# ADS1298.net
KiCad netlist of a schematic drawn in Altium Designer
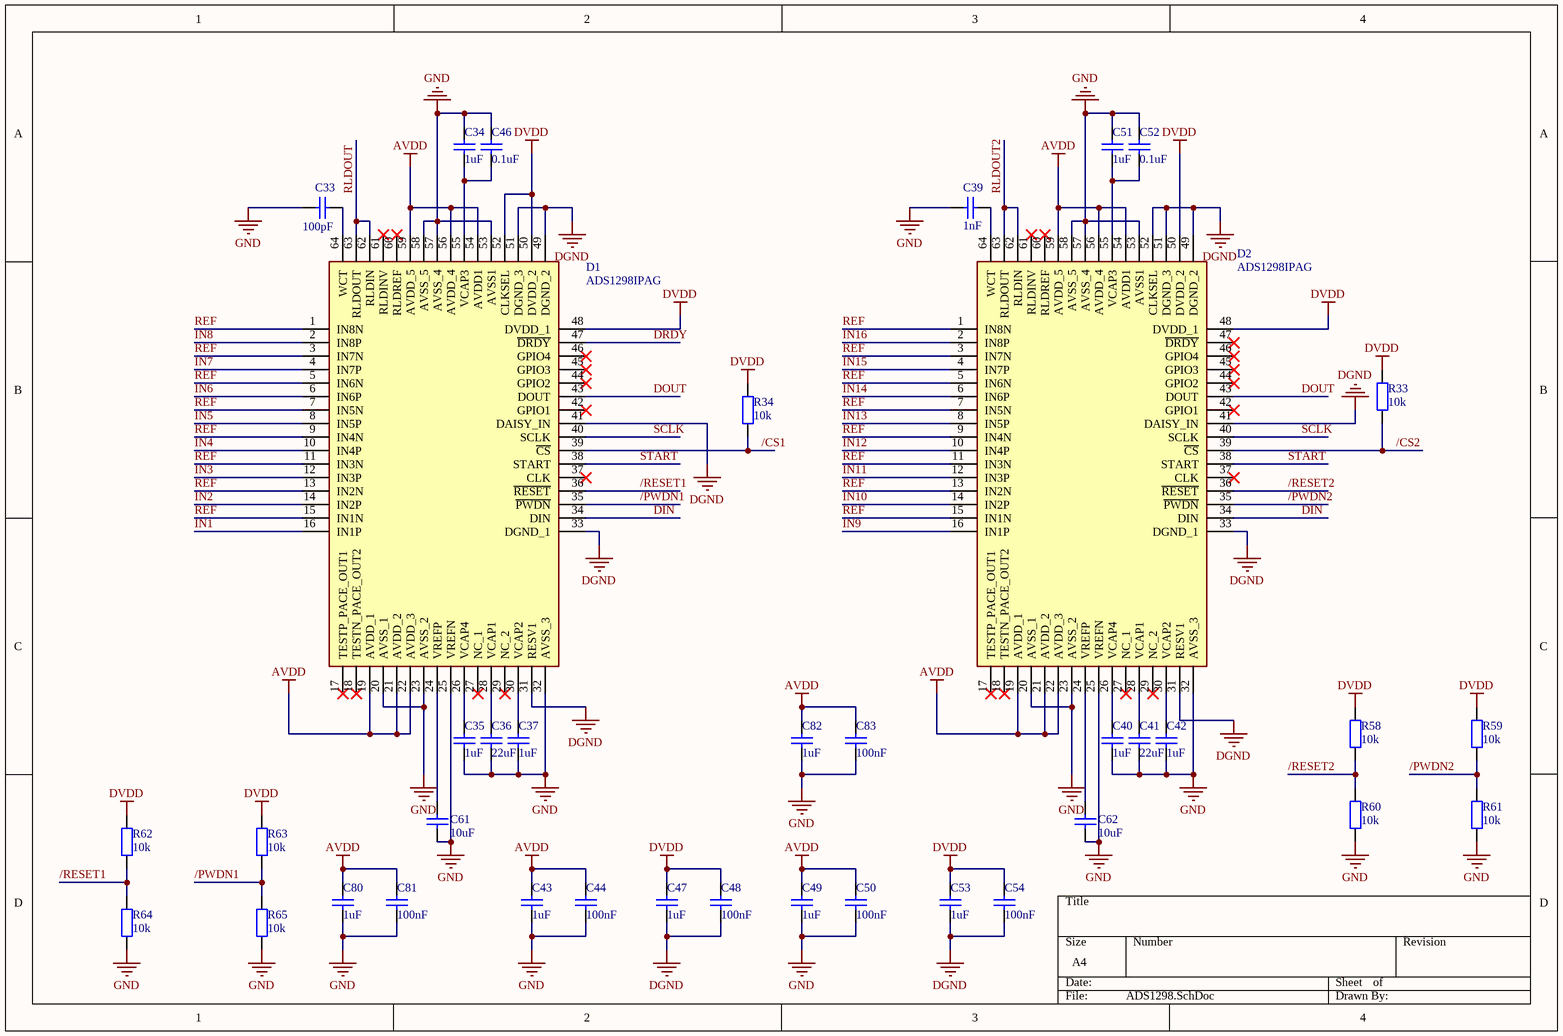
[diagram p0: ADS1298.SchDoc]

(export (version "E")
  (design (tool "Eeschema 10.0.6"))
  (components
    (comp (ref "C33")
      (value "100pF")
      (footprint "C0603")
      (description "Capacitor")
      (fields (field (name "PUBLISHER") "Altium Limited"))
      (libsource (lib "Miscellaneous Devices") (part "Cap"))
    )
    (comp (ref "C34")
      (value "1uF")
      (footprint "C0603")
      (description "Capacitor")
      (fields (field (name "PUBLISHER") "Altium Limited"))
      (libsource (lib "Miscellaneous Devices") (part "Cap"))
    )
    (comp (ref "C35")
      (value "1uF")
      (footprint "C0603")
      (description "Capacitor")
      (fields (field (name "PUBLISHER") "Altium Limited"))
      (libsource (lib "Miscellaneous Devices") (part "Cap"))
    )
    (comp (ref "C36")
      (value "22uF")
      (footprint "C0603")
      (description "Capacitor")
      (fields (field (name "PUBLISHER") "Altium Limited"))
      (libsource (lib "Miscellaneous Devices") (part "Cap"))
    )
    (comp (ref "C37")
      (value "1uF")
      (footprint "C0603")
      (description "Capacitor")
      (fields (field (name "PUBLISHER") "Altium Limited"))
      (libsource (lib "Miscellaneous Devices") (part "Cap"))
    )
    (comp (ref "C39")
      (value "1nF")
      (footprint "C0603")
      (description "Capacitor")
      (fields (field (name "PUBLISHER") "Altium Limited"))
      (libsource (lib "Miscellaneous Devices") (part "Cap"))
    )
    (comp (ref "C40")
      (value "1uF")
      (footprint "C0603")
      (description "Capacitor")
      (fields (field (name "PUBLISHER") "Altium Limited"))
      (libsource (lib "Miscellaneous Devices") (part "Cap"))
    )
    (comp (ref "C41")
      (value "22uF")
      (footprint "C0603")
      (description "Capacitor")
      (fields (field (name "PUBLISHER") "Altium Limited"))
      (libsource (lib "Miscellaneous Devices") (part "Cap"))
    )
    (comp (ref "C42")
      (value "1uF")
      (footprint "C0603")
      (description "Capacitor")
      (fields (field (name "PUBLISHER") "Altium Limited"))
      (libsource (lib "Miscellaneous Devices") (part "Cap"))
    )
    (comp (ref "C43")
      (value "1uF")
      (footprint "C0603")
      (description "Capacitor")
      (fields (field (name "PUBLISHER") "Altium Limited"))
      (libsource (lib "Miscellaneous Devices") (part "Cap"))
    )
    (comp (ref "C44")
      (value "100nF")
      (footprint "C0603")
      (description "Capacitor")
      (fields (field (name "PUBLISHER") "Altium Limited"))
      (libsource (lib "Miscellaneous Devices") (part "Cap"))
    )
    (comp (ref "C46")
      (value "0.1uF")
      (footprint "C0603")
      (description "Capacitor")
      (fields (field (name "PUBLISHER") "Altium Limited"))
      (libsource (lib "Miscellaneous Devices") (part "Cap"))
    )
    (comp (ref "C47")
      (value "1uF")
      (footprint "C0603")
      (description "Capacitor")
      (fields (field (name "PUBLISHER") "Altium Limited"))
      (libsource (lib "Miscellaneous Devices") (part "Cap"))
    )
    (comp (ref "C48")
      (value "100nF")
      (footprint "C0603")
      (description "Capacitor")
      (fields (field (name "PUBLISHER") "Altium Limited"))
      (libsource (lib "Miscellaneous Devices") (part "Cap"))
    )
    (comp (ref "C49")
      (value "1uF")
      (footprint "C0603")
      (description "Capacitor")
      (fields (field (name "PUBLISHER") "Altium Limited"))
      (libsource (lib "Miscellaneous Devices") (part "Cap"))
    )
    (comp (ref "C50")
      (value "100nF")
      (footprint "C0603")
      (description "Capacitor")
      (fields (field (name "PUBLISHER") "Altium Limited"))
      (libsource (lib "Miscellaneous Devices") (part "Cap"))
    )
    (comp (ref "C51")
      (value "1uF")
      (footprint "C0603")
      (description "Capacitor")
      (fields (field (name "PUBLISHER") "Altium Limited"))
      (libsource (lib "Miscellaneous Devices") (part "Cap"))
    )
    (comp (ref "C52")
      (value "0.1uF")
      (footprint "C0603")
      (description "Capacitor")
      (fields (field (name "PUBLISHER") "Altium Limited"))
      (libsource (lib "Miscellaneous Devices") (part "Cap"))
    )
    (comp (ref "C53")
      (value "1uF")
      (footprint "C0603")
      (description "Capacitor")
      (fields (field (name "PUBLISHER") "Altium Limited"))
      (libsource (lib "Miscellaneous Devices") (part "Cap"))
    )
    (comp (ref "C54")
      (value "100nF")
      (footprint "C0603")
      (description "Capacitor")
      (fields (field (name "PUBLISHER") "Altium Limited"))
      (libsource (lib "Miscellaneous Devices") (part "Cap"))
    )
    (comp (ref "C61")
      (value "10uF")
      (footprint "C0603")
      (description "Capacitor")
      (fields (field (name "PUBLISHER") "Altium Limited"))
      (libsource (lib "Miscellaneous Devices") (part "Cap"))
    )
    (comp (ref "C62")
      (value "10uF")
      (footprint "C0603")
      (description "Capacitor")
      (fields (field (name "PUBLISHER") "Altium Limited"))
      (libsource (lib "Miscellaneous Devices") (part "Cap"))
    )
    (comp (ref "C80")
      (value "1uF")
      (footprint "C0603")
      (description "Capacitor")
      (fields (field (name "PUBLISHER") "Altium Limited"))
      (libsource (lib "Miscellaneous Devices") (part "Cap"))
    )
    (comp (ref "C81")
      (value "100nF")
      (footprint "C0603")
      (description "Capacitor")
      (fields (field (name "PUBLISHER") "Altium Limited"))
      (libsource (lib "Miscellaneous Devices") (part "Cap"))
    )
    (comp (ref "C82")
      (value "1uF")
      (footprint "C0603")
      (description "Capacitor")
      (fields (field (name "PUBLISHER") "Altium Limited"))
      (libsource (lib "Miscellaneous Devices") (part "Cap"))
    )
    (comp (ref "C83")
      (value "100nF")
      (footprint "C0603")
      (description "Capacitor")
      (fields (field (name "PUBLISHER") "Altium Limited"))
      (libsource (lib "Miscellaneous Devices") (part "Cap"))
    )
    (comp (ref "D1")
      (value "ADS1298IPAG")
      (footprint "ADS1298")
      (description "Integrated Circuit")
      (fields (field (name "MOUSER PART NUMBER") "595-ADS1298IPAG"))
      (libsource (lib "*") (part "ADS1298IPAG"))
    )
    (comp (ref "D2")
      (value "ADS1298IPAG")
      (footprint "ADS1298")
      (description "Integrated Circuit")
      (fields (field (name "MOUSER PART NUMBER") "595-ADS1298IPAG"))
      (libsource (lib "*") (part "ADS1298IPAG"))
    )
    (comp (ref "R33")
      (value "10k")
      (footprint "RES0603")
      (description "Resistor")
      (fields (field (name "PUBLISHER") "Altium Limited"))
      (libsource (lib "Miscellaneous Devices") (part "Res2"))
    )
    (comp (ref "R34")
      (value "10k")
      (footprint "RES0603")
      (description "Resistor")
      (fields (field (name "PUBLISHER") "Altium Limited"))
      (libsource (lib "Miscellaneous Devices") (part "Res2"))
    )
    (comp (ref "R58")
      (value "10k")
      (footprint "RES0603")
      (description "Resistor")
      (fields (field (name "PUBLISHER") "Altium Limited"))
      (libsource (lib "Miscellaneous Devices") (part "Res2"))
    )
    (comp (ref "R59")
      (value "10k")
      (footprint "RES0603")
      (description "Resistor")
      (fields (field (name "PUBLISHER") "Altium Limited"))
      (libsource (lib "Miscellaneous Devices") (part "Res2"))
    )
    (comp (ref "R60")
      (value "10k")
      (footprint "RES0603")
      (description "Resistor")
      (fields (field (name "PUBLISHER") "Altium Limited"))
      (libsource (lib "Miscellaneous Devices") (part "Res2"))
    )
    (comp (ref "R61")
      (value "10k")
      (footprint "RES0603")
      (description "Resistor")
      (fields (field (name "PUBLISHER") "Altium Limited"))
      (libsource (lib "Miscellaneous Devices") (part "Res2"))
    )
    (comp (ref "R62")
      (value "10k")
      (footprint "RES0603")
      (description "Resistor")
      (fields (field (name "PUBLISHER") "Altium Limited"))
      (libsource (lib "Miscellaneous Devices") (part "Res2"))
    )
    (comp (ref "R63")
      (value "10k")
      (footprint "RES0603")
      (description "Resistor")
      (fields (field (name "PUBLISHER") "Altium Limited"))
      (libsource (lib "Miscellaneous Devices") (part "Res2"))
    )
    (comp (ref "R64")
      (value "10k")
      (footprint "RES0603")
      (description "Resistor")
      (fields (field (name "PUBLISHER") "Altium Limited"))
      (libsource (lib "Miscellaneous Devices") (part "Res2"))
    )
    (comp (ref "R65")
      (value "10k")
      (footprint "RES0603")
      (description "Resistor")
      (fields (field (name "PUBLISHER") "Altium Limited"))
      (libsource (lib "Miscellaneous Devices") (part "Res2"))
    )
  )
  (nets
    (net (code "1") (name "/DIN") (class "Default")
      (node (ref "D1") (pin "34") (pinfunction "DIN_34") (pintype "passive"))
      (node (ref "D2") (pin "34") (pinfunction "DIN_34") (pintype "passive"))
    )
    (net (code "2") (name "/DOUT") (class "Default")
      (node (ref "D1") (pin "43") (pinfunction "DOUT_43") (pintype "passive"))
      (node (ref "D2") (pin "43") (pinfunction "DOUT_43") (pintype "passive"))
    )
    (net (code "3") (name "/DRDY") (class "Default")
      (node (ref "D1") (pin "47") (pinfunction "~{DRDY}_47") (pintype "passive"))
    )
    (net (code "4") (name "/IN1") (class "Default")
      (node (ref "D1") (pin "16") (pinfunction "IN1P_16") (pintype "passive"))
    )
    (net (code "5") (name "/IN2") (class "Default")
      (node (ref "D1") (pin "14") (pinfunction "IN2P_14") (pintype "passive"))
    )
    (net (code "6") (name "/IN3") (class "Default")
      (node (ref "D1") (pin "12") (pinfunction "IN3P_12") (pintype "passive"))
    )
    (net (code "7") (name "/IN4") (class "Default")
      (node (ref "D1") (pin "10") (pinfunction "IN4P_10") (pintype "passive"))
    )
    (net (code "8") (name "/IN5") (class "Default")
      (node (ref "D1") (pin "8") (pinfunction "IN5P_8") (pintype "passive"))
    )
    (net (code "9") (name "/IN6") (class "Default")
      (node (ref "D1") (pin "6") (pinfunction "IN6P_6") (pintype "passive"))
    )
    (net (code "10") (name "/IN7") (class "Default")
      (node (ref "D1") (pin "4") (pinfunction "IN7P_4") (pintype "passive"))
    )
    (net (code "11") (name "/IN8") (class "Default")
      (node (ref "D1") (pin "2") (pinfunction "IN8P_2") (pintype "passive"))
    )
    (net (code "12") (name "/IN9") (class "Default")
      (node (ref "D2") (pin "16") (pinfunction "IN1P_16") (pintype "passive"))
    )
    (net (code "13") (name "/IN10") (class "Default")
      (node (ref "D2") (pin "14") (pinfunction "IN2P_14") (pintype "passive"))
    )
    (net (code "14") (name "/IN11") (class "Default")
      (node (ref "D2") (pin "12") (pinfunction "IN3P_12") (pintype "passive"))
    )
    (net (code "15") (name "/IN12") (class "Default")
      (node (ref "D2") (pin "10") (pinfunction "IN4P_10") (pintype "passive"))
    )
    (net (code "16") (name "/IN13") (class "Default")
      (node (ref "D2") (pin "8") (pinfunction "IN5P_8") (pintype "passive"))
    )
    (net (code "17") (name "/IN14") (class "Default")
      (node (ref "D2") (pin "6") (pinfunction "IN6P_6") (pintype "passive"))
    )
    (net (code "18") (name "/IN15") (class "Default")
      (node (ref "D2") (pin "4") (pinfunction "IN7P_4") (pintype "passive"))
    )
    (net (code "19") (name "/IN16") (class "Default")
      (node (ref "D2") (pin "2") (pinfunction "IN8P_2") (pintype "passive"))
    )
    (net (code "20") (name "/REF") (class "Default")
      (node (ref "D1") (pin "1") (pinfunction "IN8N_1") (pintype "passive"))
      (node (ref "D1") (pin "11") (pinfunction "IN3N_11") (pintype "passive"))
      (node (ref "D1") (pin "13") (pinfunction "IN2N_13") (pintype "passive"))
      (node (ref "D1") (pin "15") (pinfunction "IN1N_15") (pintype "passive"))
      (node (ref "D1") (pin "3") (pinfunction "IN7N_3") (pintype "passive"))
      (node (ref "D1") (pin "5") (pinfunction "IN6N_5") (pintype "passive"))
      (node (ref "D1") (pin "7") (pinfunction "IN5N_7") (pintype "passive"))
      (node (ref "D1") (pin "9") (pinfunction "IN4N_9") (pintype "passive"))
      (node (ref "D2") (pin "1") (pinfunction "IN8N_1") (pintype "passive"))
      (node (ref "D2") (pin "11") (pinfunction "IN3N_11") (pintype "passive"))
      (node (ref "D2") (pin "13") (pinfunction "IN2N_13") (pintype "passive"))
      (node (ref "D2") (pin "15") (pinfunction "IN1N_15") (pintype "passive"))
      (node (ref "D2") (pin "3") (pinfunction "IN7N_3") (pintype "passive"))
      (node (ref "D2") (pin "5") (pinfunction "IN6N_5") (pintype "passive"))
      (node (ref "D2") (pin "7") (pinfunction "IN5N_7") (pintype "passive"))
      (node (ref "D2") (pin "9") (pinfunction "IN4N_9") (pintype "passive"))
    )
    (net (code "21") (name "/RLDOUT") (class "Default")
      (node (ref "D1") (pin "62") (pinfunction "RLDIN_62") (pintype "passive"))
      (node (ref "D1") (pin "63") (pinfunction "RLDOUT_63") (pintype "passive"))
    )
    (net (code "22") (name "/RLDOUT2") (class "Default")
      (node (ref "D2") (pin "62") (pinfunction "RLDIN_62") (pintype "passive"))
      (node (ref "D2") (pin "63") (pinfunction "RLDOUT_63") (pintype "passive"))
    )
    (net (code "23") (name "/SCLK") (class "Default")
      (node (ref "D1") (pin "40") (pinfunction "SCLK_40") (pintype "passive"))
      (node (ref "D2") (pin "40") (pinfunction "SCLK_40") (pintype "passive"))
    )
    (net (code "24") (name "/START") (class "Default")
      (node (ref "D1") (pin "38") (pinfunction "START_38") (pintype "passive"))
      (node (ref "D2") (pin "38") (pinfunction "START_38") (pintype "passive"))
    )
    (net (code "25") (name "/{slash}CS1") (class "Default")
      (node (ref "D1") (pin "39") (pinfunction "~{CS}_39") (pintype "passive"))
      (node (ref "R34") (pin "1") (pinfunction "1_1") (pintype "passive"))
    )
    (net (code "26") (name "/{slash}CS2") (class "Default")
      (node (ref "D2") (pin "39") (pinfunction "~{CS}_39") (pintype "passive"))
      (node (ref "R33") (pin "1") (pinfunction "1_1") (pintype "passive"))
    )
    (net (code "27") (name "/{slash}PWDN1") (class "Default")
      (node (ref "D1") (pin "35") (pinfunction "~{PWDN}_35") (pintype "passive"))
      (node (ref "R63") (pin "1") (pinfunction "1_1") (pintype "passive"))
      (node (ref "R65") (pin "2") (pinfunction "2_2") (pintype "passive"))
    )
    (net (code "28") (name "/{slash}PWDN2") (class "Default")
      (node (ref "D2") (pin "35") (pinfunction "~{PWDN}_35") (pintype "passive"))
      (node (ref "R59") (pin "1") (pinfunction "1_1") (pintype "passive"))
      (node (ref "R61") (pin "2") (pinfunction "2_2") (pintype "passive"))
    )
    (net (code "29") (name "/{slash}RESET1") (class "Default")
      (node (ref "D1") (pin "36") (pinfunction "~{RESET}_36") (pintype "passive"))
      (node (ref "R62") (pin "1") (pinfunction "1_1") (pintype "passive"))
      (node (ref "R64") (pin "2") (pinfunction "2_2") (pintype "passive"))
    )
    (net (code "30") (name "/{slash}RESET2") (class "Default")
      (node (ref "D2") (pin "36") (pinfunction "~{RESET}_36") (pintype "passive"))
      (node (ref "R58") (pin "1") (pinfunction "1_1") (pintype "passive"))
      (node (ref "R60") (pin "2") (pinfunction "2_2") (pintype "passive"))
    )
    (net (code "31") (name "AVDD") (class "Default")
      (node (ref "C43") (pin "1") (pinfunction "1_1") (pintype "passive"))
      (node (ref "C44") (pin "1") (pinfunction "1_1") (pintype "passive"))
      (node (ref "C49") (pin "1") (pinfunction "1_1") (pintype "passive"))
      (node (ref "C50") (pin "1") (pinfunction "1_1") (pintype "passive"))
      (node (ref "C80") (pin "1") (pinfunction "1_1") (pintype "passive"))
      (node (ref "C81") (pin "1") (pinfunction "1_1") (pintype "passive"))
      (node (ref "C82") (pin "1") (pinfunction "1_1") (pintype "passive"))
      (node (ref "C83") (pin "1") (pinfunction "1_1") (pintype "passive"))
      (node (ref "D1") (pin "19") (pinfunction "AVDD_1_19") (pintype "passive"))
      (node (ref "D1") (pin "21") (pinfunction "AVDD_2_21") (pintype "passive"))
      (node (ref "D1") (pin "22") (pinfunction "AVDD_3_22") (pintype "passive"))
      (node (ref "D1") (pin "54") (pinfunction "AVDD1_54") (pintype "passive"))
      (node (ref "D1") (pin "56") (pinfunction "AVDD_4_56") (pintype "passive"))
      (node (ref "D1") (pin "59") (pinfunction "AVDD_5_59") (pintype "passive"))
      (node (ref "D2") (pin "19") (pinfunction "AVDD_1_19") (pintype "passive"))
      (node (ref "D2") (pin "21") (pinfunction "AVDD_2_21") (pintype "passive"))
      (node (ref "D2") (pin "22") (pinfunction "AVDD_3_22") (pintype "passive"))
      (node (ref "D2") (pin "54") (pinfunction "AVDD1_54") (pintype "passive"))
      (node (ref "D2") (pin "56") (pinfunction "AVDD_4_56") (pintype "passive"))
      (node (ref "D2") (pin "59") (pinfunction "AVDD_5_59") (pintype "passive"))
    )
    (net (code "32") (name "DGND") (class "Default")
      (node (ref "C47") (pin "2") (pinfunction "2_2") (pintype "passive"))
      (node (ref "C48") (pin "2") (pinfunction "2_2") (pintype "passive"))
      (node (ref "C53") (pin "2") (pinfunction "2_2") (pintype "passive"))
      (node (ref "C54") (pin "2") (pinfunction "2_2") (pintype "passive"))
      (node (ref "D1") (pin "31") (pinfunction "RESV1_31") (pintype "passive"))
      (node (ref "D1") (pin "33") (pinfunction "DGND_1_33") (pintype "passive"))
      (node (ref "D1") (pin "41") (pinfunction "DAISY_IN_41") (pintype "passive"))
      (node (ref "D1") (pin "49") (pinfunction "DGND_2_49") (pintype "passive"))
      (node (ref "D1") (pin "51") (pinfunction "DGND_3_51") (pintype "passive"))
      (node (ref "D2") (pin "31") (pinfunction "RESV1_31") (pintype "passive"))
      (node (ref "D2") (pin "33") (pinfunction "DGND_1_33") (pintype "passive"))
      (node (ref "D2") (pin "41") (pinfunction "DAISY_IN_41") (pintype "passive"))
      (node (ref "D2") (pin "49") (pinfunction "DGND_2_49") (pintype "passive"))
      (node (ref "D2") (pin "51") (pinfunction "DGND_3_51") (pintype "passive"))
      (node (ref "D2") (pin "52") (pinfunction "CLKSEL_52") (pintype "passive"))
    )
    (net (code "33") (name "DVDD") (class "Default")
      (node (ref "C47") (pin "1") (pinfunction "1_1") (pintype "passive"))
      (node (ref "C48") (pin "1") (pinfunction "1_1") (pintype "passive"))
      (node (ref "C53") (pin "1") (pinfunction "1_1") (pintype "passive"))
      (node (ref "C54") (pin "1") (pinfunction "1_1") (pintype "passive"))
      (node (ref "D1") (pin "48") (pinfunction "DVDD_1_48") (pintype "passive"))
      (node (ref "D1") (pin "50") (pinfunction "DVDD_2_50") (pintype "passive"))
      (node (ref "D1") (pin "52") (pinfunction "CLKSEL_52") (pintype "passive"))
      (node (ref "D2") (pin "48") (pinfunction "DVDD_1_48") (pintype "passive"))
      (node (ref "D2") (pin "50") (pinfunction "DVDD_2_50") (pintype "passive"))
      (node (ref "R33") (pin "2") (pinfunction "2_2") (pintype "passive"))
      (node (ref "R34") (pin "2") (pinfunction "2_2") (pintype "passive"))
      (node (ref "R58") (pin "2") (pinfunction "2_2") (pintype "passive"))
      (node (ref "R59") (pin "2") (pinfunction "2_2") (pintype "passive"))
      (node (ref "R62") (pin "2") (pinfunction "2_2") (pintype "passive"))
      (node (ref "R63") (pin "2") (pinfunction "2_2") (pintype "passive"))
    )
    (net (code "34") (name "GND") (class "Default")
      (node (ref "C33") (pin "2") (pinfunction "2_2") (pintype "passive"))
      (node (ref "C34") (pin "2") (pinfunction "2_2") (pintype "passive"))
      (node (ref "C35") (pin "2") (pinfunction "2_2") (pintype "passive"))
      (node (ref "C36") (pin "2") (pinfunction "2_2") (pintype "passive"))
      (node (ref "C37") (pin "2") (pinfunction "2_2") (pintype "passive"))
      (node (ref "C39") (pin "2") (pinfunction "2_2") (pintype "passive"))
      (node (ref "C40") (pin "2") (pinfunction "2_2") (pintype "passive"))
      (node (ref "C41") (pin "2") (pinfunction "2_2") (pintype "passive"))
      (node (ref "C42") (pin "2") (pinfunction "2_2") (pintype "passive"))
      (node (ref "C43") (pin "2") (pinfunction "2_2") (pintype "passive"))
      (node (ref "C44") (pin "2") (pinfunction "2_2") (pintype "passive"))
      (node (ref "C46") (pin "2") (pinfunction "2_2") (pintype "passive"))
      (node (ref "C49") (pin "2") (pinfunction "2_2") (pintype "passive"))
      (node (ref "C50") (pin "2") (pinfunction "2_2") (pintype "passive"))
      (node (ref "C51") (pin "2") (pinfunction "2_2") (pintype "passive"))
      (node (ref "C52") (pin "2") (pinfunction "2_2") (pintype "passive"))
      (node (ref "C61") (pin "1") (pinfunction "1_1") (pintype "passive"))
      (node (ref "C62") (pin "1") (pinfunction "1_1") (pintype "passive"))
      (node (ref "C80") (pin "2") (pinfunction "2_2") (pintype "passive"))
      (node (ref "C81") (pin "2") (pinfunction "2_2") (pintype "passive"))
      (node (ref "C82") (pin "2") (pinfunction "2_2") (pintype "passive"))
      (node (ref "C83") (pin "2") (pinfunction "2_2") (pintype "passive"))
      (node (ref "D1") (pin "20") (pinfunction "AVSS_1_20") (pintype "passive"))
      (node (ref "D1") (pin "23") (pinfunction "AVSS_2_23") (pintype "passive"))
      (node (ref "D1") (pin "25") (pinfunction "VREFN_25") (pintype "passive"))
      (node (ref "D1") (pin "32") (pinfunction "AVSS_3_32") (pintype "passive"))
      (node (ref "D1") (pin "53") (pinfunction "AVSS1_53") (pintype "passive"))
      (node (ref "D1") (pin "57") (pinfunction "AVSS_4_57") (pintype "passive"))
      (node (ref "D1") (pin "58") (pinfunction "AVSS_5_58") (pintype "passive"))
      (node (ref "D2") (pin "20") (pinfunction "AVSS_1_20") (pintype "passive"))
      (node (ref "D2") (pin "23") (pinfunction "AVSS_2_23") (pintype "passive"))
      (node (ref "D2") (pin "25") (pinfunction "VREFN_25") (pintype "passive"))
      (node (ref "D2") (pin "32") (pinfunction "AVSS_3_32") (pintype "passive"))
      (node (ref "D2") (pin "53") (pinfunction "AVSS1_53") (pintype "passive"))
      (node (ref "D2") (pin "57") (pinfunction "AVSS_4_57") (pintype "passive"))
      (node (ref "D2") (pin "58") (pinfunction "AVSS_5_58") (pintype "passive"))
      (node (ref "R60") (pin "1") (pinfunction "1_1") (pintype "passive"))
      (node (ref "R61") (pin "1") (pinfunction "1_1") (pintype "passive"))
      (node (ref "R64") (pin "1") (pinfunction "1_1") (pintype "passive"))
      (node (ref "R65") (pin "1") (pinfunction "1_1") (pintype "passive"))
    )
    (net (code "35") (name "Net-(D1-VCAP1)") (class "Default")
      (node (ref "C36") (pin "1") (pinfunction "1_1") (pintype "passive"))
      (node (ref "D1") (pin "28") (pinfunction "VCAP1_28") (pintype "passive"))
    )
    (net (code "36") (name "Net-(D1-VCAP2)") (class "Default")
      (node (ref "C37") (pin "1") (pinfunction "1_1") (pintype "passive"))
      (node (ref "D1") (pin "30") (pinfunction "VCAP2_30") (pintype "passive"))
    )
    (net (code "37") (name "Net-(D1-VCAP3)") (class "Default")
      (node (ref "C34") (pin "1") (pinfunction "1_1") (pintype "passive"))
      (node (ref "C46") (pin "1") (pinfunction "1_1") (pintype "passive"))
      (node (ref "D1") (pin "55") (pinfunction "VCAP3_55") (pintype "passive"))
    )
    (net (code "38") (name "Net-(D1-VCAP4)") (class "Default")
      (node (ref "C35") (pin "1") (pinfunction "1_1") (pintype "passive"))
      (node (ref "D1") (pin "26") (pinfunction "VCAP4_26") (pintype "passive"))
    )
    (net (code "39") (name "Net-(D1-VREFP)") (class "Default")
      (node (ref "C61") (pin "2") (pinfunction "2_2") (pintype "passive"))
      (node (ref "D1") (pin "24") (pinfunction "VREFP_24") (pintype "passive"))
    )
    (net (code "40") (name "Net-(D1-WCT)") (class "Default")
      (node (ref "C33") (pin "1") (pinfunction "1_1") (pintype "passive"))
      (node (ref "D1") (pin "64") (pinfunction "WCT_64") (pintype "passive"))
    )
    (net (code "41") (name "Net-(D2-VCAP1)") (class "Default")
      (node (ref "C41") (pin "1") (pinfunction "1_1") (pintype "passive"))
      (node (ref "D2") (pin "28") (pinfunction "VCAP1_28") (pintype "passive"))
    )
    (net (code "42") (name "Net-(D2-VCAP2)") (class "Default")
      (node (ref "C42") (pin "1") (pinfunction "1_1") (pintype "passive"))
      (node (ref "D2") (pin "30") (pinfunction "VCAP2_30") (pintype "passive"))
    )
    (net (code "43") (name "Net-(D2-VCAP3)") (class "Default")
      (node (ref "C51") (pin "1") (pinfunction "1_1") (pintype "passive"))
      (node (ref "C52") (pin "1") (pinfunction "1_1") (pintype "passive"))
      (node (ref "D2") (pin "55") (pinfunction "VCAP3_55") (pintype "passive"))
    )
    (net (code "44") (name "Net-(D2-VCAP4)") (class "Default")
      (node (ref "C40") (pin "1") (pinfunction "1_1") (pintype "passive"))
      (node (ref "D2") (pin "26") (pinfunction "VCAP4_26") (pintype "passive"))
    )
    (net (code "45") (name "Net-(D2-VREFP)") (class "Default")
      (node (ref "C62") (pin "2") (pinfunction "2_2") (pintype "passive"))
      (node (ref "D2") (pin "24") (pinfunction "VREFP_24") (pintype "passive"))
    )
    (net (code "46") (name "Net-(D2-WCT)") (class "Default")
      (node (ref "C39") (pin "1") (pinfunction "1_1") (pintype "passive"))
      (node (ref "D2") (pin "64") (pinfunction "WCT_64") (pintype "passive"))
    )
    (net (code "47") (name "unconnected-(D1-CLK-Pad37)") (class "Default")
      (node (ref "D1") (pin "37") (pinfunction "CLK_37") (pintype "passive+no_connect"))
    )
    (net (code "48") (name "unconnected-(D1-GPIO1-Pad42)") (class "Default")
      (node (ref "D1") (pin "42") (pinfunction "GPIO1_42") (pintype "passive+no_connect"))
    )
    (net (code "49") (name "unconnected-(D1-GPIO2-Pad44)") (class "Default")
      (node (ref "D1") (pin "44") (pinfunction "GPIO2_44") (pintype "passive+no_connect"))
    )
    (net (code "50") (name "unconnected-(D1-GPIO3-Pad45)") (class "Default")
      (node (ref "D1") (pin "45") (pinfunction "GPIO3_45") (pintype "passive+no_connect"))
    )
    (net (code "51") (name "unconnected-(D1-GPIO4-Pad46)") (class "Default")
      (node (ref "D1") (pin "46") (pinfunction "GPIO4_46") (pintype "passive+no_connect"))
    )
    (net (code "52") (name "unconnected-(D1-NC_1-Pad27)") (class "Default")
      (node (ref "D1") (pin "27") (pinfunction "NC_1_27") (pintype "passive+no_connect"))
    )
    (net (code "53") (name "unconnected-(D1-NC_2-Pad29)") (class "Default")
      (node (ref "D1") (pin "29") (pinfunction "NC_2_29") (pintype "passive+no_connect"))
    )
    (net (code "54") (name "unconnected-(D1-RLDINV-Pad61)") (class "Default")
      (node (ref "D1") (pin "61") (pinfunction "RLDINV_61") (pintype "passive+no_connect"))
    )
    (net (code "55") (name "unconnected-(D1-RLDREF-Pad60)") (class "Default")
      (node (ref "D1") (pin "60") (pinfunction "RLDREF_60") (pintype "passive+no_connect"))
    )
    (net (code "56") (name "unconnected-(D1-TESTN_PACE_OUT2-Pad18)") (class "Default")
      (node (ref "D1") (pin "18") (pinfunction "TESTN_PACE_OUT2_18") (pintype "passive+no_connect"))
    )
    (net (code "57") (name "unconnected-(D1-TESTP_PACE_OUT1-Pad17)") (class "Default")
      (node (ref "D1") (pin "17") (pinfunction "TESTP_PACE_OUT1_17") (pintype "passive+no_connect"))
    )
    (net (code "58") (name "unconnected-(D2-CLK-Pad37)") (class "Default")
      (node (ref "D2") (pin "37") (pinfunction "CLK_37") (pintype "passive+no_connect"))
    )
    (net (code "59") (name "unconnected-(D2-GPIO1-Pad42)") (class "Default")
      (node (ref "D2") (pin "42") (pinfunction "GPIO1_42") (pintype "passive+no_connect"))
    )
    (net (code "60") (name "unconnected-(D2-GPIO2-Pad44)") (class "Default")
      (node (ref "D2") (pin "44") (pinfunction "GPIO2_44") (pintype "passive+no_connect"))
    )
    (net (code "61") (name "unconnected-(D2-GPIO3-Pad45)") (class "Default")
      (node (ref "D2") (pin "45") (pinfunction "GPIO3_45") (pintype "passive+no_connect"))
    )
    (net (code "62") (name "unconnected-(D2-GPIO4-Pad46)") (class "Default")
      (node (ref "D2") (pin "46") (pinfunction "GPIO4_46") (pintype "passive+no_connect"))
    )
    (net (code "63") (name "unconnected-(D2-NC_1-Pad27)") (class "Default")
      (node (ref "D2") (pin "27") (pinfunction "NC_1_27") (pintype "passive+no_connect"))
    )
    (net (code "64") (name "unconnected-(D2-NC_2-Pad29)") (class "Default")
      (node (ref "D2") (pin "29") (pinfunction "NC_2_29") (pintype "passive+no_connect"))
    )
    (net (code "65") (name "unconnected-(D2-RLDINV-Pad61)") (class "Default")
      (node (ref "D2") (pin "61") (pinfunction "RLDINV_61") (pintype "passive+no_connect"))
    )
    (net (code "66") (name "unconnected-(D2-RLDREF-Pad60)") (class "Default")
      (node (ref "D2") (pin "60") (pinfunction "RLDREF_60") (pintype "passive+no_connect"))
    )
    (net (code "67") (name "unconnected-(D2-TESTN_PACE_OUT2-Pad18)") (class "Default")
      (node (ref "D2") (pin "18") (pinfunction "TESTN_PACE_OUT2_18") (pintype "passive+no_connect"))
    )
    (net (code "68") (name "unconnected-(D2-TESTP_PACE_OUT1-Pad17)") (class "Default")
      (node (ref "D2") (pin "17") (pinfunction "TESTP_PACE_OUT1_17") (pintype "passive+no_connect"))
    )
    (net (code "69") (name "unconnected-(D2-~{DRDY}-Pad47)") (class "Default")
      (node (ref "D2") (pin "47") (pinfunction "~{DRDY}_47") (pintype "passive+no_connect"))
    )
  )
)
